# esp32.net
KiCad netlist of a schematic drawn in Altium Designer
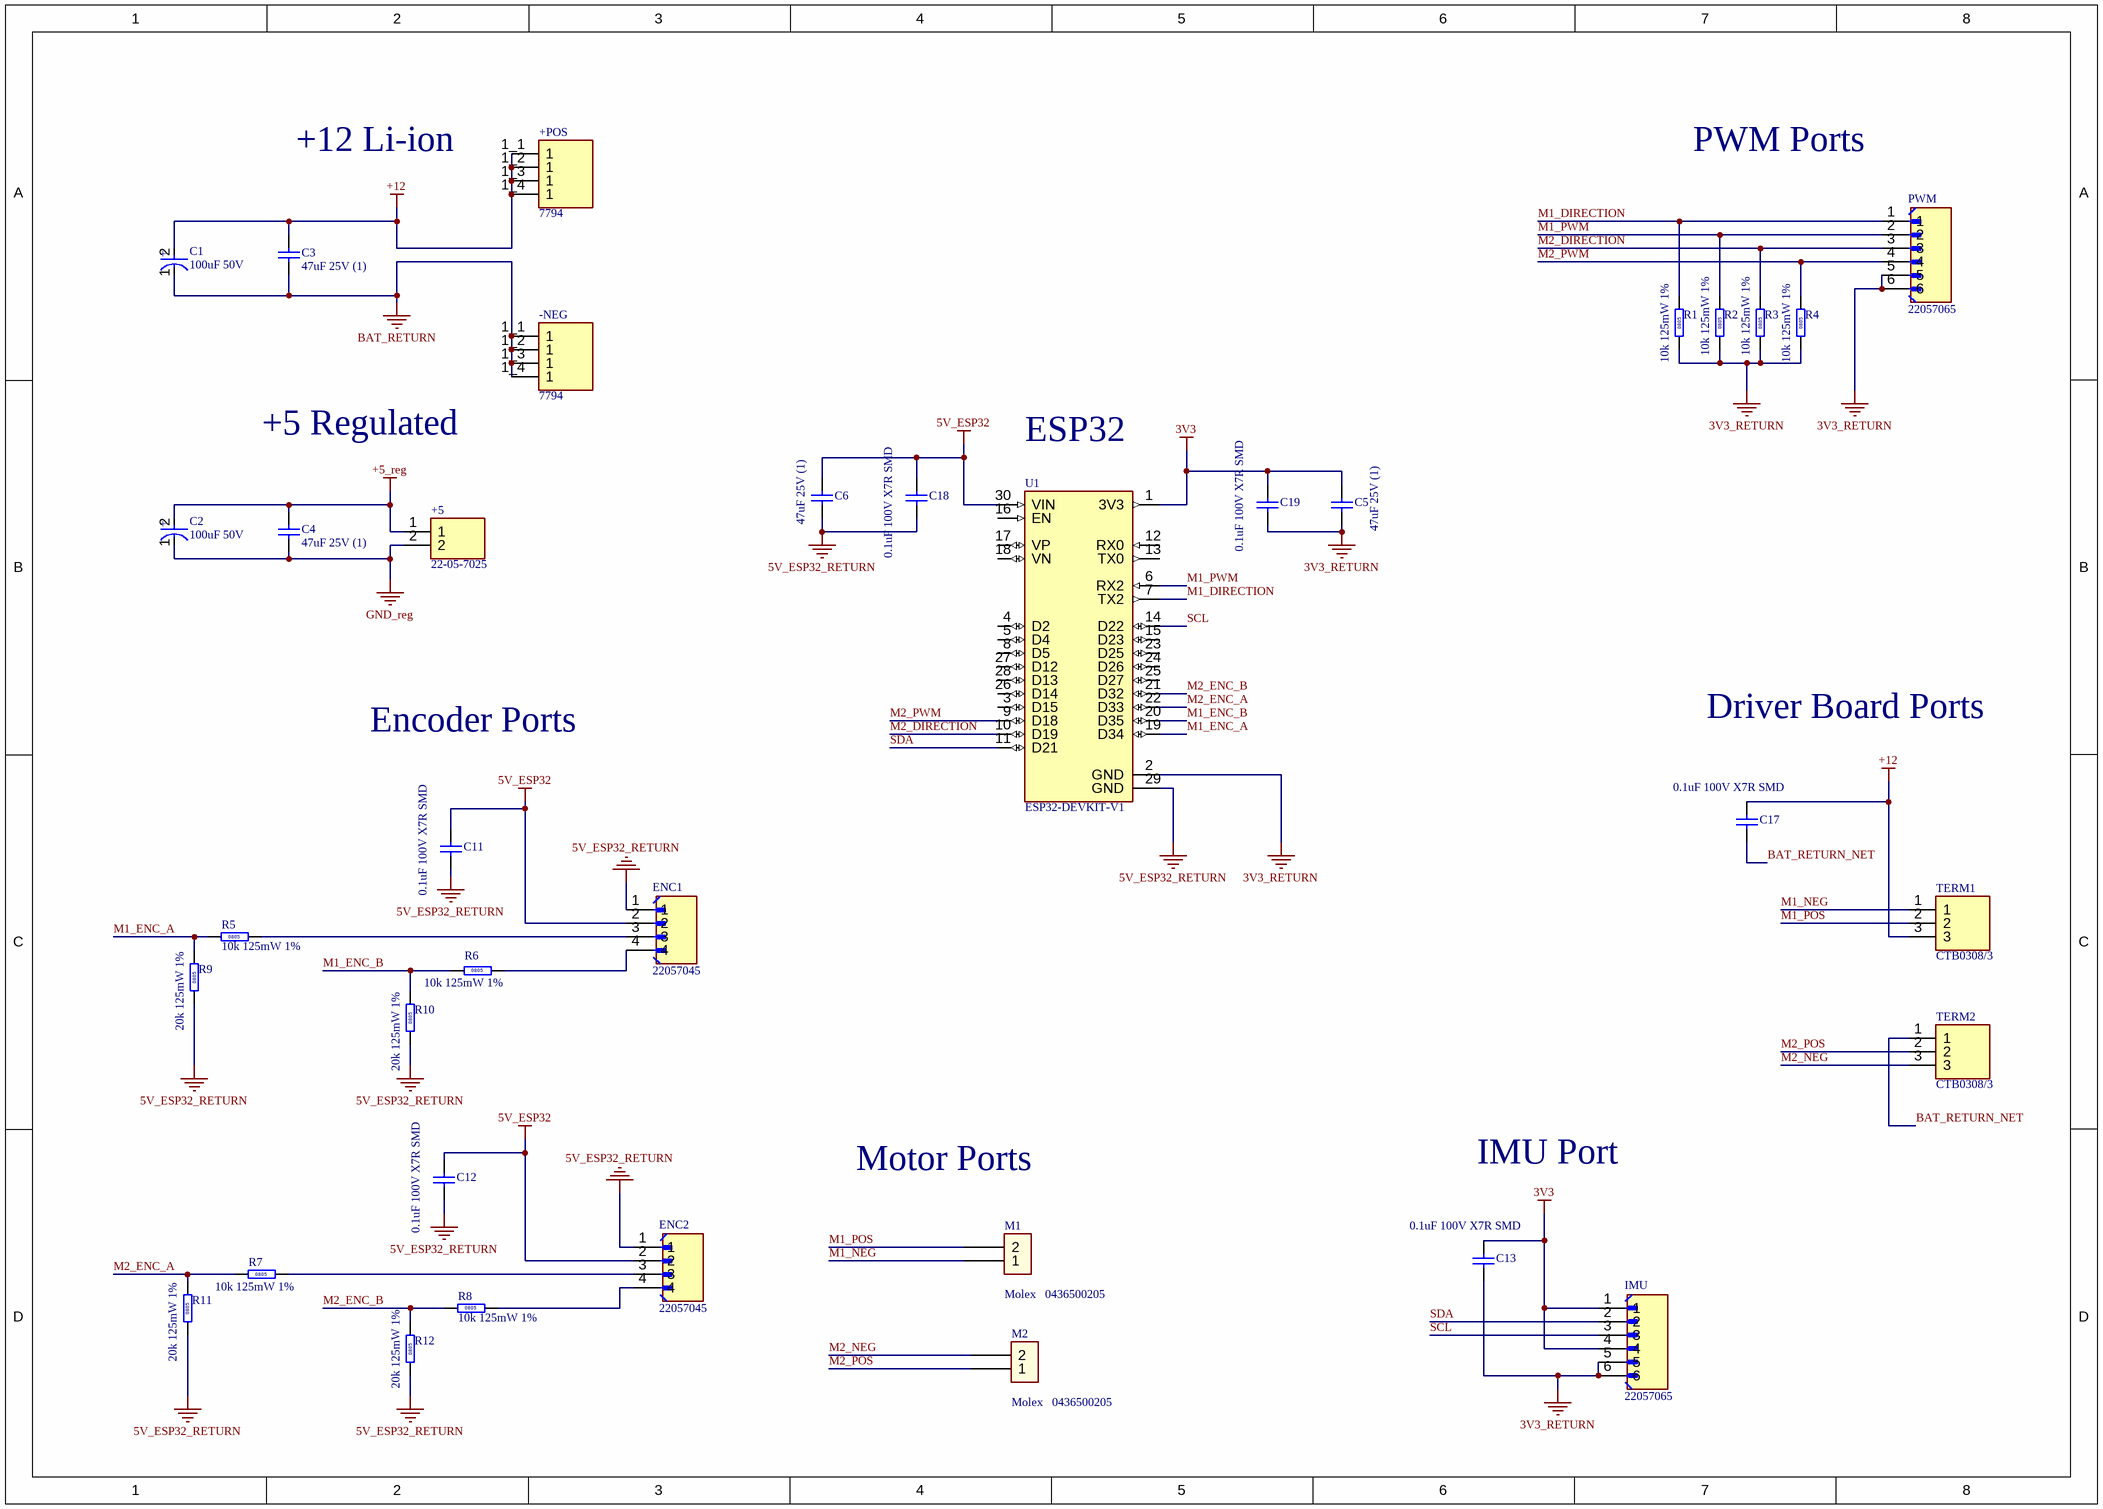
[diagram p0: esp32.SchDoc]

(export (version "E")
  (design (tool "Eeschema 10.0.6"))
  (components
    (comp (ref "+5")
      (value "22-05-7025")
      (footprint "MOLEX_22-05-7025")
      (description "Header 2.5mm SPOX, WTB, RA, F/lock, 2w ¦ Molex Incorporated 22-05-7025")
      (fields (field (name "MF") "Molex"))
      (libsource (lib "22-05-7025") (part "22-05-7025"))
    )
    (comp (ref "+POS")
      (value "7794")
      (footprint "KEYSTONE_7794")
      (description "PC SCREW TERMINAL ¦ Keystone Electronics 7794")
      (fields (field (name "MF") "Keystone Electronics"))
      (libsource (lib "7794_new") (part "7794"))
    )
    (comp (ref "-NEG")
      (value "7794")
      (footprint "KEYSTONE_7794")
      (description "PC SCREW TERMINAL ¦ Keystone Electronics 7794")
      (fields (field (name "MF") "Keystone Electronics"))
      (libsource (lib "7794_new") (part "7794"))
    )
    (comp (ref "C1")
      (value "100uF 50V")
      (footprint "FP-SF-MFG")
      (fields
        (field (name "TOLERANCE") "20%")
        (field (name "MANUFACTURER") "Panasonic")
        (field (name "MANUFACTURERPARTNUMBER") "EEE-1HA101UP")
      )
      (libsource (lib "Andor Technology") (part "cf48714ba7e38822c1575c7ec0b6d1f"))
    )
    (comp (ref "C2")
      (value "100uF 50V")
      (footprint "FP-SF-MFG")
      (fields
        (field (name "TOLERANCE") "20%")
        (field (name "MANUFACTURER") "Panasonic")
        (field (name "MANUFACTURERPARTNUMBER") "EEE-1HA101UP")
      )
      (libsource (lib "Andor Technology") (part "cf48714ba7e38822c1575c7ec0b6d1f"))
    )
    (comp (ref "C3")
      (value "47uF 25V (1)")
      (footprint "1206 CAP")
      (fields
        (field (name "MANUFACTURERPARTNUMBER") "C3216X5R1E476M160AC")
        (field (name "TOLERANCE") "20%")
        (field (name "MANUFACTURER") "TDK")
      )
      (libsource (lib "Andor Technology") (part "CAP"))
    )
    (comp (ref "C4")
      (value "47uF 25V (1)")
      (footprint "1206 CAP")
      (fields
        (field (name "MANUFACTURERPARTNUMBER") "C3216X5R1E476M160AC")
        (field (name "TOLERANCE") "20%")
        (field (name "MANUFACTURER") "TDK")
      )
      (libsource (lib "Andor Technology") (part "CAP"))
    )
    (comp (ref "C5")
      (value "47uF 25V (1)")
      (footprint "1206 CAP")
      (fields
        (field (name "MANUFACTURERPARTNUMBER") "C3216X5R1E476M160AC")
        (field (name "TOLERANCE") "20%")
        (field (name "MANUFACTURER") "TDK")
      )
      (libsource (lib "Andor Technology") (part "CAP"))
    )
    (comp (ref "C6")
      (value "47uF 25V (1)")
      (footprint "1206 CAP")
      (fields
        (field (name "MANUFACTURERPARTNUMBER") "C3216X5R1E476M160AC")
        (field (name "TOLERANCE") "20%")
        (field (name "MANUFACTURER") "TDK")
      )
      (libsource (lib "Andor Technology") (part "CAP"))
    )
    (comp (ref "C11")
      (value "0.1uF 100V X7R SMD")
      (footprint "FP-C1206C-EB-MFG")
      (description "Cap, SMD, 0.1uF, 100V, 10%, 1206, X7R")
      (fields (field (name "MANUFACTURERPARTNUMBER") "C1206C104K1RAC7800") (field (name "TOLERANCE") "10%"))
      (libsource (lib "Andor Technology") (part "b4654b650e69147ec39a6b967a45e02"))
    )
    (comp (ref "C12")
      (value "0.1uF 100V X7R SMD")
      (footprint "FP-C1206C-EB-MFG")
      (description "Cap, SMD, 0.1uF, 100V, 10%, 1206, X7R")
      (fields (field (name "MANUFACTURERPARTNUMBER") "C1206C104K1RAC7800") (field (name "TOLERANCE") "10%"))
      (libsource (lib "Andor Technology") (part "b4654b650e69147ec39a6b967a45e02"))
    )
    (comp (ref "C13")
      (value "0.1uF 100V X7R SMD")
      (footprint "FP-C1206C-EB-MFG")
      (description "Cap, SMD, 0.1uF, 100V, 10%, 1206, X7R")
      (fields (field (name "MANUFACTURERPARTNUMBER") "C1206C104K1RAC7800") (field (name "TOLERANCE") "10%"))
      (libsource (lib "Andor Technology") (part "b4654b650e69147ec39a6b967a45e02"))
    )
    (comp (ref "C17")
      (value "0.1uF 100V X7R SMD")
      (footprint "FP-C1206C-EB-MFG")
      (description "Cap, SMD, 0.1uF, 100V, 10%, 1206, X7R")
      (fields (field (name "MANUFACTURERPARTNUMBER") "C1206C104K1RAC7800") (field (name "TOLERANCE") "10%"))
      (libsource (lib "Andor Technology") (part "b4654b650e69147ec39a6b967a45e02"))
    )
    (comp (ref "C18")
      (value "0.1uF 100V X7R SMD")
      (footprint "FP-C1206C-EB-MFG")
      (description "Cap, SMD, 0.1uF, 100V, 10%, 1206, X7R")
      (fields (field (name "MANUFACTURERPARTNUMBER") "C1206C104K1RAC7800") (field (name "TOLERANCE") "10%"))
      (libsource (lib "Andor Technology") (part "b4654b650e69147ec39a6b967a45e02"))
    )
    (comp (ref "C19")
      (value "0.1uF 100V X7R SMD")
      (footprint "FP-C1206C-EB-MFG")
      (description "Cap, SMD, 0.1uF, 100V, 10%, 1206, X7R")
      (fields (field (name "MANUFACTURERPARTNUMBER") "C1206C104K1RAC7800") (field (name "TOLERANCE") "10%"))
      (libsource (lib "Andor Technology") (part "b4654b650e69147ec39a6b967a45e02"))
    )
    (comp (ref "ENC1")
      (value "22057045")
      (footprint "MOLEX_22057045")
      (libsource (lib "Andor Technology") (part "22057045"))
    )
    (comp (ref "ENC2")
      (value "22057045")
      (footprint "MOLEX_22057045")
      (libsource (lib "Andor Technology") (part "22057045"))
    )
    (comp (ref "IMU")
      (value "22057065")
      (footprint "MOLEX_22057065")
      (description "Conn Shrouded Header (4 Sides) HDR 6 POS 2.5mm Solder RA Side Entry Thru-Hole SPOXâ„¢ Bag")
      (fields (field (name "MF") "Molex"))
      (libsource (lib "22057065") (part "22057065"))
    )
    (comp (ref "M1")
      (value "Molex 	\r\n0436500205")
      (footprint "MOLEX-0436500205")
      (description "Conn, TH, Micro-Fit, 2 Way, 1 Row, 3mm pitch, Jack, Right-Angled")
      (fields (field (name "MANUFACTURERPARTNUMBER") "0436500205") (field (name "MANUFACTURER") "Molex"))
      (libsource (lib "Andor Technology") (part "2-Way Connector"))
    )
    (comp (ref "M2")
      (value "Molex 	\r\n0436500205")
      (footprint "MOLEX-0436500205")
      (description "Conn, TH, Micro-Fit, 2 Way, 1 Row, 3mm pitch, Jack, Right-Angled")
      (fields (field (name "MANUFACTURERPARTNUMBER") "0436500205") (field (name "MANUFACTURER") "Molex"))
      (libsource (lib "Andor Technology") (part "2-Way Connector"))
    )
    (comp (ref "PWM")
      (value "22057065")
      (footprint "MOLEX_22057065")
      (description "Conn Shrouded Header (4 Sides) HDR 6 POS 2.5mm Solder RA Side Entry Thru-Hole SPOXâ„¢ Bag")
      (fields (field (name "MF") "Molex"))
      (libsource (lib "22057065") (part "22057065"))
    )
    (comp (ref "R1")
      (value "10k 125mW 1%")
      (footprint "RESC2013X60X35ML10T20")
      (description "Res, SMD, 10k, 125mW, 1%, ±200ppm, 0805")
      (fields
        (field (name "MANUFACTURER") "Panasonic")
        (field (name "MANUFACTURERPARTNUMBER") "ERJ-6GEYJ103V")
      )
      (libsource (lib "Andor Technology") (part "Resistor_0805"))
    )
    (comp (ref "R2")
      (value "10k 125mW 1%")
      (footprint "RESC2013X60X35ML10T20")
      (description "Res, SMD, 10k, 125mW, 1%, ±200ppm, 0805")
      (fields
        (field (name "MANUFACTURER") "Panasonic")
        (field (name "MANUFACTURERPARTNUMBER") "ERJ-6GEYJ103V")
      )
      (libsource (lib "Andor Technology") (part "Resistor_0805"))
    )
    (comp (ref "R3")
      (value "10k 125mW 1%")
      (footprint "RESC2013X60X35ML10T20")
      (description "Res, SMD, 10k, 125mW, 1%, ±200ppm, 0805")
      (fields
        (field (name "MANUFACTURER") "Panasonic")
        (field (name "MANUFACTURERPARTNUMBER") "ERJ-6GEYJ103V")
      )
      (libsource (lib "Andor Technology") (part "Resistor_0805"))
    )
    (comp (ref "R4")
      (value "10k 125mW 1%")
      (footprint "RESC2013X60X35ML10T20")
      (description "Res, SMD, 10k, 125mW, 1%, ±200ppm, 0805")
      (fields
        (field (name "MANUFACTURER") "Panasonic")
        (field (name "MANUFACTURERPARTNUMBER") "ERJ-6GEYJ103V")
      )
      (libsource (lib "Andor Technology") (part "Resistor_0805"))
    )
    (comp (ref "R5")
      (value "10k 125mW 1%")
      (footprint "RESC2013X60X35ML10T20")
      (description "Res, SMD, 10k, 125mW, 1%, ±200ppm, 0805")
      (fields
        (field (name "MANUFACTURER") "Panasonic")
        (field (name "MANUFACTURERPARTNUMBER") "ERJ-6GEYJ103V")
      )
      (libsource (lib "") (part "Resistor_0805_1"))
    )
    (comp (ref "R6")
      (value "10k 125mW 1%")
      (footprint "RESC2013X60X35ML10T20")
      (description "Res, SMD, 10k, 125mW, 1%, ±200ppm, 0805")
      (fields
        (field (name "MANUFACTURER") "Panasonic")
        (field (name "MANUFACTURERPARTNUMBER") "ERJ-6GEYJ103V")
      )
      (libsource (lib "") (part "Resistor_0805_1"))
    )
    (comp (ref "R7")
      (value "10k 125mW 1%")
      (footprint "RESC2013X60X35ML10T20")
      (description "Res, SMD, 10k, 125mW, 1%, ±200ppm, 0805")
      (fields
        (field (name "MANUFACTURER") "Panasonic")
        (field (name "MANUFACTURERPARTNUMBER") "ERJ-6GEYJ103V")
      )
      (libsource (lib "") (part "Resistor_0805_1"))
    )
    (comp (ref "R8")
      (value "10k 125mW 1%")
      (footprint "RESC2013X60X35ML10T20")
      (description "Res, SMD, 10k, 125mW, 1%, ±200ppm, 0805")
      (fields
        (field (name "MANUFACTURER") "Panasonic")
        (field (name "MANUFACTURERPARTNUMBER") "ERJ-6GEYJ103V")
      )
      (libsource (lib "") (part "Resistor_0805_1"))
    )
    (comp (ref "R9")
      (value "20k 125mW 1%")
      (footprint "RESC2013X60X35ML10T20")
      (description "Res, SMD, 10k, 125mW, 1%, ±200ppm, 0805")
      (fields
        (field (name "MANUFACTURER") "Panasonic")
        (field (name "MANUFACTURERPARTNUMBER") "ERJ-6GEYJ103V")
      )
      (libsource (lib "Andor Technology") (part "Resistor_0805"))
    )
    (comp (ref "R10")
      (value "20k 125mW 1%")
      (footprint "RESC2013X60X35ML10T20")
      (description "Res, SMD, 10k, 125mW, 1%, ±200ppm, 0805")
      (fields
        (field (name "MANUFACTURER") "Panasonic")
        (field (name "MANUFACTURERPARTNUMBER") "ERJ-6GEYJ103V")
      )
      (libsource (lib "Andor Technology") (part "Resistor_0805"))
    )
    (comp (ref "R11")
      (value "20k 125mW 1%")
      (footprint "RESC2013X60X35ML10T20")
      (description "Res, SMD, 10k, 125mW, 1%, ±200ppm, 0805")
      (fields
        (field (name "MANUFACTURER") "Panasonic")
        (field (name "MANUFACTURERPARTNUMBER") "ERJ-6GEYJ103V")
      )
      (libsource (lib "Andor Technology") (part "Resistor_0805"))
    )
    (comp (ref "R12")
      (value "20k 125mW 1%")
      (footprint "RESC2013X60X35ML10T20")
      (description "Res, SMD, 10k, 125mW, 1%, ±200ppm, 0805")
      (fields
        (field (name "MANUFACTURER") "Panasonic")
        (field (name "MANUFACTURERPARTNUMBER") "ERJ-6GEYJ103V")
      )
      (libsource (lib "Andor Technology") (part "Resistor_0805"))
    )
    (comp (ref "TERM1")
      (value "CTB0308/3")
      (footprint "CTB0308_3-Footprint-1")
      (description "Barrier Strip Terminal Block, 3 position")
      (fields (field (name "MANUFACTURERPARTNUMBER") "CTB0308_3") (field (name "MANUFACTURER") "CAMDENBOSS"))
      (libsource (lib "Andor Technology") (part "CTB0308_3-Symbol-1"))
    )
    (comp (ref "TERM2")
      (value "CTB0308/3")
      (footprint "CTB0308_3-Footprint-1")
      (description "Barrier Strip Terminal Block, 3 position")
      (fields (field (name "MANUFACTURERPARTNUMBER") "CTB0308_3") (field (name "MANUFACTURER") "CAMDENBOSS"))
      (libsource (lib "Andor Technology") (part "CTB0308_3-Symbol-1"))
    )
    (comp (ref "U1")
      (value "ESP32-DEVKIT-V1")
      (footprint "MODULE_ESP32_DEVKIT_V1")
      (fields (field (name "MF") "Do it"))
      (libsource (lib "ESP32-DEVKIT-V1") (part "ESP32-DEVKIT-V1"))
    )
  )
  (nets
    (net (code "1") (name "+5_reg") (class "Default")
      (node (ref "+5") (pin "1") (pinfunction "1_1") (pintype "passive"))
      (node (ref "C2") (pin "2") (pinfunction "A_2") (pintype "passive"))
      (node (ref "C4") (pin "2") (pinfunction "2_2") (pintype "passive"))
    )
    (net (code "2") (name "+12") (class "Default")
      (node (ref "+POS") (pin "1_1") (pinfunction "1_1_1") (pintype "passive"))
      (node (ref "+POS") (pin "1_2") (pinfunction "1_1_2") (pintype "passive"))
      (node (ref "+POS") (pin "1_3") (pinfunction "1_1_3") (pintype "passive"))
      (node (ref "+POS") (pin "1_4") (pinfunction "1_1_4") (pintype "passive"))
      (node (ref "C1") (pin "2") (pinfunction "A_2") (pintype "passive"))
      (node (ref "C17") (pin "2") (pinfunction "2_2") (pintype "passive"))
      (node (ref "C3") (pin "2") (pinfunction "2_2") (pintype "passive"))
      (node (ref "TERM1") (pin "3") (pinfunction "3_3") (pintype "passive"))
    )
    (net (code "3") (name "/BAT_RETURN_NET") (class "Default")
      (node (ref "C17") (pin "1") (pinfunction "1_1") (pintype "passive"))
      (node (ref "TERM2") (pin "1") (pinfunction "1_1") (pintype "passive"))
    )
    (net (code "4") (name "/M1_DIRECTION") (class "Default")
      (node (ref "PWM") (pin "1") (pinfunction "1_1") (pintype "passive"))
      (node (ref "R1") (pin "2") (pinfunction "2_2") (pintype "passive"))
      (node (ref "U1") (pin "7") (pinfunction "TX2_7") (pintype "output"))
    )
    (net (code "5") (name "/M1_ENC_A") (class "Default")
      (node (ref "R5") (pin "1") (pinfunction "1_1") (pintype "passive"))
      (node (ref "R9") (pin "2") (pinfunction "2_2") (pintype "passive"))
      (node (ref "U1") (pin "19") (pinfunction "D34_19") (pintype "bidirectional"))
    )
    (net (code "6") (name "/M1_ENC_B") (class "Default")
      (node (ref "R10") (pin "2") (pinfunction "2_2") (pintype "passive"))
      (node (ref "R6") (pin "1") (pinfunction "1_1") (pintype "passive"))
      (node (ref "U1") (pin "20") (pinfunction "D35_20") (pintype "bidirectional"))
    )
    (net (code "7") (name "/M1_NEG") (class "Default")
      (node (ref "M1") (pin "1") (pinfunction "1_1") (pintype "passive"))
      (node (ref "TERM1") (pin "1") (pinfunction "1_1") (pintype "passive"))
    )
    (net (code "8") (name "/M1_POS") (class "Default")
      (node (ref "M1") (pin "2") (pinfunction "2_2") (pintype "passive"))
      (node (ref "TERM1") (pin "2") (pinfunction "2_2") (pintype "passive"))
    )
    (net (code "9") (name "/M1_PWM") (class "Default")
      (node (ref "PWM") (pin "2") (pinfunction "2_2") (pintype "passive"))
      (node (ref "R2") (pin "2") (pinfunction "2_2") (pintype "passive"))
      (node (ref "U1") (pin "6") (pinfunction "RX2_6") (pintype "input"))
    )
    (net (code "10") (name "/M2_DIRECTION") (class "Default")
      (node (ref "PWM") (pin "3") (pinfunction "3_3") (pintype "passive"))
      (node (ref "R3") (pin "2") (pinfunction "2_2") (pintype "passive"))
      (node (ref "U1") (pin "10") (pinfunction "D19_10") (pintype "bidirectional"))
    )
    (net (code "11") (name "/M2_ENC_A") (class "Default")
      (node (ref "R11") (pin "2") (pinfunction "2_2") (pintype "passive"))
      (node (ref "R7") (pin "1") (pinfunction "1_1") (pintype "passive"))
      (node (ref "U1") (pin "22") (pinfunction "D33_22") (pintype "bidirectional"))
    )
    (net (code "12") (name "/M2_ENC_B") (class "Default")
      (node (ref "R12") (pin "2") (pinfunction "2_2") (pintype "passive"))
      (node (ref "R8") (pin "1") (pinfunction "1_1") (pintype "passive"))
      (node (ref "U1") (pin "21") (pinfunction "D32_21") (pintype "bidirectional"))
    )
    (net (code "13") (name "/M2_NEG") (class "Default")
      (node (ref "M2") (pin "2") (pinfunction "2_2") (pintype "passive"))
      (node (ref "TERM2") (pin "3") (pinfunction "3_3") (pintype "passive"))
    )
    (net (code "14") (name "/M2_POS") (class "Default")
      (node (ref "M2") (pin "1") (pinfunction "1_1") (pintype "passive"))
      (node (ref "TERM2") (pin "2") (pinfunction "2_2") (pintype "passive"))
    )
    (net (code "15") (name "/M2_PWM") (class "Default")
      (node (ref "PWM") (pin "4") (pinfunction "4_4") (pintype "passive"))
      (node (ref "R4") (pin "2") (pinfunction "2_2") (pintype "passive"))
      (node (ref "U1") (pin "9") (pinfunction "D18_9") (pintype "bidirectional"))
    )
    (net (code "16") (name "/SCL") (class "Default")
      (node (ref "IMU") (pin "3") (pinfunction "3_3") (pintype "passive"))
      (node (ref "U1") (pin "14") (pinfunction "D22_14") (pintype "bidirectional"))
    )
    (net (code "17") (name "/SDA") (class "Default")
      (node (ref "IMU") (pin "2") (pinfunction "2_2") (pintype "passive"))
      (node (ref "U1") (pin "11") (pinfunction "D21_11") (pintype "bidirectional"))
    )
    (net (code "18") (name "3V3") (class "Default")
      (node (ref "C13") (pin "2") (pinfunction "2_2") (pintype "passive"))
      (node (ref "C19") (pin "2") (pinfunction "2_2") (pintype "passive"))
      (node (ref "C5") (pin "2") (pinfunction "2_2") (pintype "passive"))
      (node (ref "IMU") (pin "1") (pinfunction "1_1") (pintype "passive"))
      (node (ref "IMU") (pin "4") (pinfunction "4_4") (pintype "passive"))
      (node (ref "U1") (pin "1") (pinfunction "3V3_1") (pintype "output"))
    )
    (net (code "19") (name "3V3_RETURN") (class "Default")
      (node (ref "C13") (pin "1") (pinfunction "1_1") (pintype "passive"))
      (node (ref "C19") (pin "1") (pinfunction "1_1") (pintype "passive"))
      (node (ref "C5") (pin "1") (pinfunction "1_1") (pintype "passive"))
      (node (ref "IMU") (pin "5") (pinfunction "5_5") (pintype "passive"))
      (node (ref "IMU") (pin "6") (pinfunction "6_6") (pintype "passive"))
      (node (ref "PWM") (pin "5") (pinfunction "5_5") (pintype "passive"))
      (node (ref "PWM") (pin "6") (pinfunction "6_6") (pintype "passive"))
      (node (ref "R1") (pin "1") (pinfunction "1_1") (pintype "passive"))
      (node (ref "R2") (pin "1") (pinfunction "1_1") (pintype "passive"))
      (node (ref "R3") (pin "1") (pinfunction "1_1") (pintype "passive"))
      (node (ref "R4") (pin "1") (pinfunction "1_1") (pintype "passive"))
      (node (ref "U1") (pin "2") (pinfunction "GND_2") (pintype "power_in"))
    )
    (net (code "20") (name "5V_ESP32") (class "Default")
      (node (ref "C11") (pin "2") (pinfunction "2_2") (pintype "passive"))
      (node (ref "C12") (pin "2") (pinfunction "2_2") (pintype "passive"))
      (node (ref "C18") (pin "2") (pinfunction "2_2") (pintype "passive"))
      (node (ref "C6") (pin "2") (pinfunction "2_2") (pintype "passive"))
      (node (ref "ENC1") (pin "2") (pinfunction "2_2") (pintype "passive"))
      (node (ref "ENC2") (pin "2") (pinfunction "2_2") (pintype "passive"))
      (node (ref "U1") (pin "30") (pinfunction "VIN_30") (pintype "input"))
    )
    (net (code "21") (name "5V_ESP32_RETURN") (class "Default")
      (node (ref "C11") (pin "1") (pinfunction "1_1") (pintype "passive"))
      (node (ref "C12") (pin "1") (pinfunction "1_1") (pintype "passive"))
      (node (ref "C18") (pin "1") (pinfunction "1_1") (pintype "passive"))
      (node (ref "C6") (pin "1") (pinfunction "1_1") (pintype "passive"))
      (node (ref "ENC1") (pin "1") (pinfunction "1_1") (pintype "passive"))
      (node (ref "ENC2") (pin "1") (pinfunction "1_1") (pintype "passive"))
      (node (ref "R10") (pin "1") (pinfunction "1_1") (pintype "passive"))
      (node (ref "R11") (pin "1") (pinfunction "1_1") (pintype "passive"))
      (node (ref "R12") (pin "1") (pinfunction "1_1") (pintype "passive"))
      (node (ref "R9") (pin "1") (pinfunction "1_1") (pintype "passive"))
      (node (ref "U1") (pin "29") (pinfunction "GND_29") (pintype "power_in"))
    )
    (net (code "22") (name "BAT_RETURN") (class "Default")
      (node (ref "-NEG") (pin "1_1") (pinfunction "1_1_1") (pintype "passive"))
      (node (ref "-NEG") (pin "1_2") (pinfunction "1_1_2") (pintype "passive"))
      (node (ref "-NEG") (pin "1_3") (pinfunction "1_1_3") (pintype "passive"))
      (node (ref "-NEG") (pin "1_4") (pinfunction "1_1_4") (pintype "passive"))
      (node (ref "C1") (pin "1") (pinfunction "C_1") (pintype "passive"))
      (node (ref "C3") (pin "1") (pinfunction "1_1") (pintype "passive"))
    )
    (net (code "23") (name "GND_reg") (class "Default")
      (node (ref "+5") (pin "2") (pinfunction "2_2") (pintype "passive"))
      (node (ref "C2") (pin "1") (pinfunction "C_1") (pintype "passive"))
      (node (ref "C4") (pin "1") (pinfunction "1_1") (pintype "passive"))
    )
    (net (code "24") (name "Net-(ENC1-Pad3)") (class "Default")
      (node (ref "ENC1") (pin "3") (pinfunction "3_3") (pintype "passive"))
      (node (ref "R5") (pin "2") (pinfunction "2_2") (pintype "passive"))
    )
    (net (code "25") (name "Net-(ENC1-Pad4)") (class "Default")
      (node (ref "ENC1") (pin "4") (pinfunction "4_4") (pintype "passive"))
      (node (ref "R6") (pin "2") (pinfunction "2_2") (pintype "passive"))
    )
    (net (code "26") (name "Net-(ENC2-Pad3)") (class "Default")
      (node (ref "ENC2") (pin "3") (pinfunction "3_3") (pintype "passive"))
      (node (ref "R7") (pin "2") (pinfunction "2_2") (pintype "passive"))
    )
    (net (code "27") (name "Net-(ENC2-Pad4)") (class "Default")
      (node (ref "ENC2") (pin "4") (pinfunction "4_4") (pintype "passive"))
      (node (ref "R8") (pin "2") (pinfunction "2_2") (pintype "passive"))
    )
    (net (code "28") (name "unconnected-(U1-D2-Pad4)") (class "Default")
      (node (ref "U1") (pin "4") (pinfunction "D2_4") (pintype "bidirectional"))
    )
    (net (code "29") (name "unconnected-(U1-D4-Pad5)") (class "Default")
      (node (ref "U1") (pin "5") (pinfunction "D4_5") (pintype "bidirectional"))
    )
    (net (code "30") (name "unconnected-(U1-D5-Pad8)") (class "Default")
      (node (ref "U1") (pin "8") (pinfunction "D5_8") (pintype "bidirectional"))
    )
    (net (code "31") (name "unconnected-(U1-D12-Pad27)") (class "Default")
      (node (ref "U1") (pin "27") (pinfunction "D12_27") (pintype "bidirectional"))
    )
    (net (code "32") (name "unconnected-(U1-D13-Pad28)") (class "Default")
      (node (ref "U1") (pin "28") (pinfunction "D13_28") (pintype "bidirectional"))
    )
    (net (code "33") (name "unconnected-(U1-D14-Pad26)") (class "Default")
      (node (ref "U1") (pin "26") (pinfunction "D14_26") (pintype "bidirectional"))
    )
    (net (code "34") (name "unconnected-(U1-D15-Pad3)") (class "Default")
      (node (ref "U1") (pin "3") (pinfunction "D15_3") (pintype "bidirectional"))
    )
    (net (code "35") (name "unconnected-(U1-D23-Pad15)") (class "Default")
      (node (ref "U1") (pin "15") (pinfunction "D23_15") (pintype "bidirectional"))
    )
    (net (code "36") (name "unconnected-(U1-D25-Pad23)") (class "Default")
      (node (ref "U1") (pin "23") (pinfunction "D25_23") (pintype "bidirectional"))
    )
    (net (code "37") (name "unconnected-(U1-D26-Pad24)") (class "Default")
      (node (ref "U1") (pin "24") (pinfunction "D26_24") (pintype "bidirectional"))
    )
    (net (code "38") (name "unconnected-(U1-D27-Pad25)") (class "Default")
      (node (ref "U1") (pin "25") (pinfunction "D27_25") (pintype "bidirectional"))
    )
    (net (code "39") (name "unconnected-(U1-EN-Pad16)") (class "Default")
      (node (ref "U1") (pin "16") (pinfunction "EN_16") (pintype "input"))
    )
    (net (code "40") (name "unconnected-(U1-RX0-Pad12)") (class "Default")
      (node (ref "U1") (pin "12") (pinfunction "RX0_12") (pintype "input"))
    )
    (net (code "41") (name "unconnected-(U1-TX0-Pad13)") (class "Default")
      (node (ref "U1") (pin "13") (pinfunction "TX0_13") (pintype "output"))
    )
    (net (code "42") (name "unconnected-(U1-VN-Pad18)") (class "Default")
      (node (ref "U1") (pin "18") (pinfunction "VN_18") (pintype "bidirectional"))
    )
    (net (code "43") (name "unconnected-(U1-VP-Pad17)") (class "Default")
      (node (ref "U1") (pin "17") (pinfunction "VP_17") (pintype "bidirectional"))
    )
  )
)
